# ProPrj_EMU_Multi_LED_Button_PCB_rev1_0.net
KiCad netlist of a schematic drawn in EasyEDA Pro
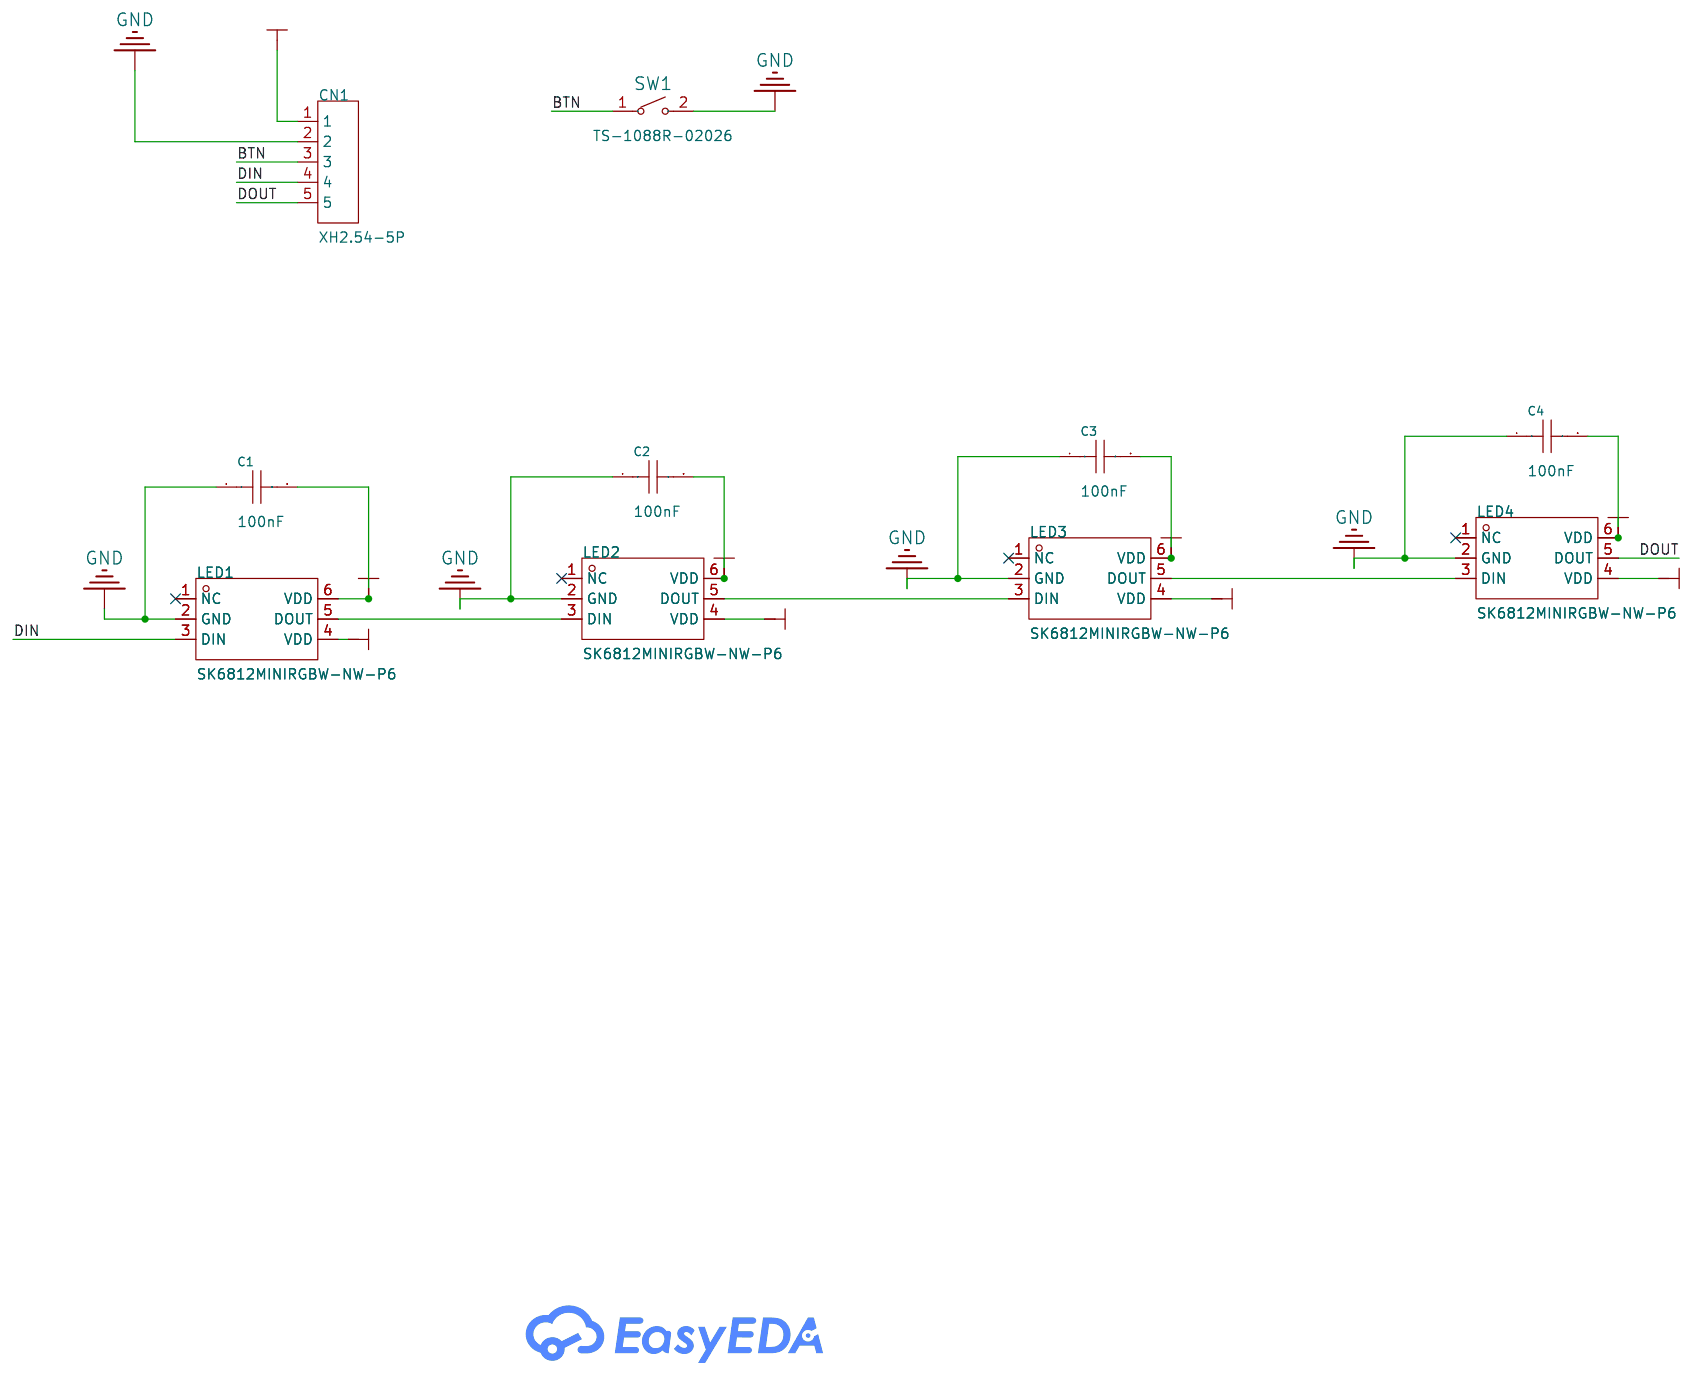
[diagram p0: schematic sheet]

(export (version "E")
  (design (tool "Eeschema 10.0.6"))
  (components
    (comp (ref "C1")
      (value "100nF")
      (footprint "easyedapro:C0603")
      (description "Capacitance:100nF Tolerance:±10% Tolerance:±10% Voltage Rating:50V Temperature Coefficient:X7R")
      (fields
        (field (name "Manufacturer Part") "CL10B104KB8NNNC")
        (field (name "Manufacturer") "SAMSUNG(三星)")
      )
      (libsource (lib "easyedapro") (part "CL10B104KB8NNNC"))
    )
    (comp (ref "C2")
      (value "100nF")
      (footprint "easyedapro:C0603")
      (description "Capacitance:100nF Tolerance:±10% Tolerance:±10% Voltage Rating:50V Temperature Coefficient:X7R")
      (fields
        (field (name "Manufacturer Part") "CL10B104KB8NNNC")
        (field (name "Manufacturer") "SAMSUNG(三星)")
      )
      (libsource (lib "easyedapro") (part "CL10B104KB8NNNC"))
    )
    (comp (ref "C3")
      (value "100nF")
      (footprint "easyedapro:C0603")
      (description "Capacitance:100nF Tolerance:±10% Tolerance:±10% Voltage Rating:50V Temperature Coefficient:X7R")
      (fields
        (field (name "Manufacturer Part") "CL10B104KB8NNNC")
        (field (name "Manufacturer") "SAMSUNG(三星)")
      )
      (libsource (lib "easyedapro") (part "CL10B104KB8NNNC"))
    )
    (comp (ref "C4")
      (value "100nF")
      (footprint "easyedapro:C0603")
      (description "Capacitance:100nF Tolerance:±10% Tolerance:±10% Voltage Rating:50V Temperature Coefficient:X7R")
      (fields
        (field (name "Manufacturer Part") "CL10B104KB8NNNC")
        (field (name "Manufacturer") "SAMSUNG(三星)")
      )
      (libsource (lib "easyedapro") (part "CL10B104KB8NNNC"))
    )
    (comp (ref "CN1")
      (value "XH2.54-5P")
      (footprint "easyedapro:CONN-TH_5P-P2.54_C9900008095")
      (libsource (lib "easyedapro") (part "XH2.54-5P_C9900017328"))
    )
    (comp (ref "LED1")
      (value "SK6812MINIRGBW-NW-P6")
      (footprint "easyedapro:LED-ARRAY-SMD_6P-L3.7-W3.5-TL-RD-1")
      (fields (field (name "Manufacturer") "欧思科光电"))
      (libsource (lib "easyedapro") (part "SK6812MINIRGBW-NW-P6"))
    )
    (comp (ref "LED2")
      (value "SK6812MINIRGBW-NW-P6")
      (footprint "easyedapro:LED-ARRAY-SMD_6P-L3.7-W3.5-TL-RD-1")
      (fields (field (name "Manufacturer") "欧思科光电"))
      (libsource (lib "easyedapro") (part "SK6812MINIRGBW-NW-P6"))
    )
    (comp (ref "LED3")
      (value "SK6812MINIRGBW-NW-P6")
      (footprint "easyedapro:LED-ARRAY-SMD_6P-L3.7-W3.5-TL-RD-1")
      (fields (field (name "Manufacturer") "欧思科光电"))
      (libsource (lib "easyedapro") (part "SK6812MINIRGBW-NW-P6"))
    )
    (comp (ref "LED4")
      (value "SK6812MINIRGBW-NW-P6")
      (footprint "easyedapro:LED-ARRAY-SMD_6P-L3.7-W3.5-TL-RD-1")
      (fields (field (name "Manufacturer") "欧思科光电"))
      (libsource (lib "easyedapro") (part "SK6812MINIRGBW-NW-P6"))
    )
    (comp (ref "SW1")
      (value "TS-1088R-02026")
      (footprint "easyedapro:SW-SMD_L3.9-W3.0-P4.45")
      (fields (field (name "Manufacturer") "XUNPU(讯普)"))
      (libsource (lib "easyedapro") (part "TS-1088R-02026"))
    )
  )
  (nets
    (net (code "1") (name "/BTN") (class "Default")
      (node (ref "CN1") (pin "3") (pinfunction "3_3") (pintype "unspecified"))
      (node (ref "SW1") (pin "1") (pinfunction "1_1") (pintype "input"))
    )
    (net (code "2") (name "/DIN") (class "Default")
      (node (ref "CN1") (pin "4") (pinfunction "4_4") (pintype "unspecified"))
      (node (ref "LED1") (pin "3") (pinfunction "DIN_3") (pintype "unspecified"))
    )
    (net (code "3") (name "/DOUT") (class "Default")
      (node (ref "CN1") (pin "5") (pinfunction "5_5") (pintype "unspecified"))
      (node (ref "LED4") (pin "5") (pinfunction "DOUT_5") (pintype "unspecified"))
    )
    (net (code "4") (name "GND") (class "Default")
      (node (ref "C1") (pin "1") (pinfunction "1_1") (pintype "input"))
      (node (ref "C2") (pin "1") (pinfunction "1_1") (pintype "input"))
      (node (ref "C3") (pin "1") (pinfunction "1_1") (pintype "input"))
      (node (ref "C4") (pin "1") (pinfunction "1_1") (pintype "input"))
      (node (ref "CN1") (pin "2") (pinfunction "2_2") (pintype "unspecified"))
      (node (ref "LED1") (pin "2") (pinfunction "GND_2") (pintype "unspecified"))
      (node (ref "LED2") (pin "2") (pinfunction "GND_2") (pintype "unspecified"))
      (node (ref "LED3") (pin "2") (pinfunction "GND_2") (pintype "unspecified"))
      (node (ref "LED4") (pin "2") (pinfunction "GND_2") (pintype "unspecified"))
      (node (ref "SW1") (pin "2") (pinfunction "2_2") (pintype "input"))
    )
    (net (code "5") (name "Net-(LED1-DOUT)") (class "Default")
      (node (ref "LED1") (pin "5") (pinfunction "DOUT_5") (pintype "unspecified"))
      (node (ref "LED2") (pin "3") (pinfunction "DIN_3") (pintype "unspecified"))
    )
    (net (code "6") (name "Net-(LED2-DOUT)") (class "Default")
      (node (ref "LED2") (pin "5") (pinfunction "DOUT_5") (pintype "unspecified"))
      (node (ref "LED3") (pin "3") (pinfunction "DIN_3") (pintype "unspecified"))
    )
    (net (code "7") (name "Net-(LED3-DOUT)") (class "Default")
      (node (ref "LED3") (pin "5") (pinfunction "DOUT_5") (pintype "unspecified"))
      (node (ref "LED4") (pin "3") (pinfunction "DIN_3") (pintype "unspecified"))
    )
    (net (code "8") (name "VCC") (class "Default")
      (node (ref "C1") (pin "2") (pinfunction "2_2") (pintype "input"))
      (node (ref "C2") (pin "2") (pinfunction "2_2") (pintype "input"))
      (node (ref "C3") (pin "2") (pinfunction "2_2") (pintype "input"))
      (node (ref "C4") (pin "2") (pinfunction "2_2") (pintype "input"))
      (node (ref "CN1") (pin "1") (pinfunction "1_1") (pintype "unspecified"))
      (node (ref "LED1") (pin "4") (pinfunction "VDD_4") (pintype "unspecified"))
      (node (ref "LED1") (pin "6") (pinfunction "VDD_6") (pintype "unspecified"))
      (node (ref "LED2") (pin "4") (pinfunction "VDD_4") (pintype "unspecified"))
      (node (ref "LED2") (pin "6") (pinfunction "VDD_6") (pintype "unspecified"))
      (node (ref "LED3") (pin "4") (pinfunction "VDD_4") (pintype "unspecified"))
      (node (ref "LED3") (pin "6") (pinfunction "VDD_6") (pintype "unspecified"))
      (node (ref "LED4") (pin "4") (pinfunction "VDD_4") (pintype "unspecified"))
      (node (ref "LED4") (pin "6") (pinfunction "VDD_6") (pintype "unspecified"))
    )
    (net (code "9") (name "unconnected-(LED1-NC-Pad1)") (class "Default")
      (node (ref "LED1") (pin "1") (pinfunction "NC_1") (pintype "unspecified+no_connect"))
    )
    (net (code "10") (name "unconnected-(LED2-NC-Pad1)") (class "Default")
      (node (ref "LED2") (pin "1") (pinfunction "NC_1") (pintype "unspecified+no_connect"))
    )
    (net (code "11") (name "unconnected-(LED3-NC-Pad1)") (class "Default")
      (node (ref "LED3") (pin "1") (pinfunction "NC_1") (pintype "unspecified+no_connect"))
    )
    (net (code "12") (name "unconnected-(LED4-NC-Pad1)") (class "Default")
      (node (ref "LED4") (pin "1") (pinfunction "NC_1") (pintype "unspecified+no_connect"))
    )
  )
)
